# Cansat2019_1516_Payload_SectionA_v03.net
KiCad netlist of a schematic drawn in EAGLE
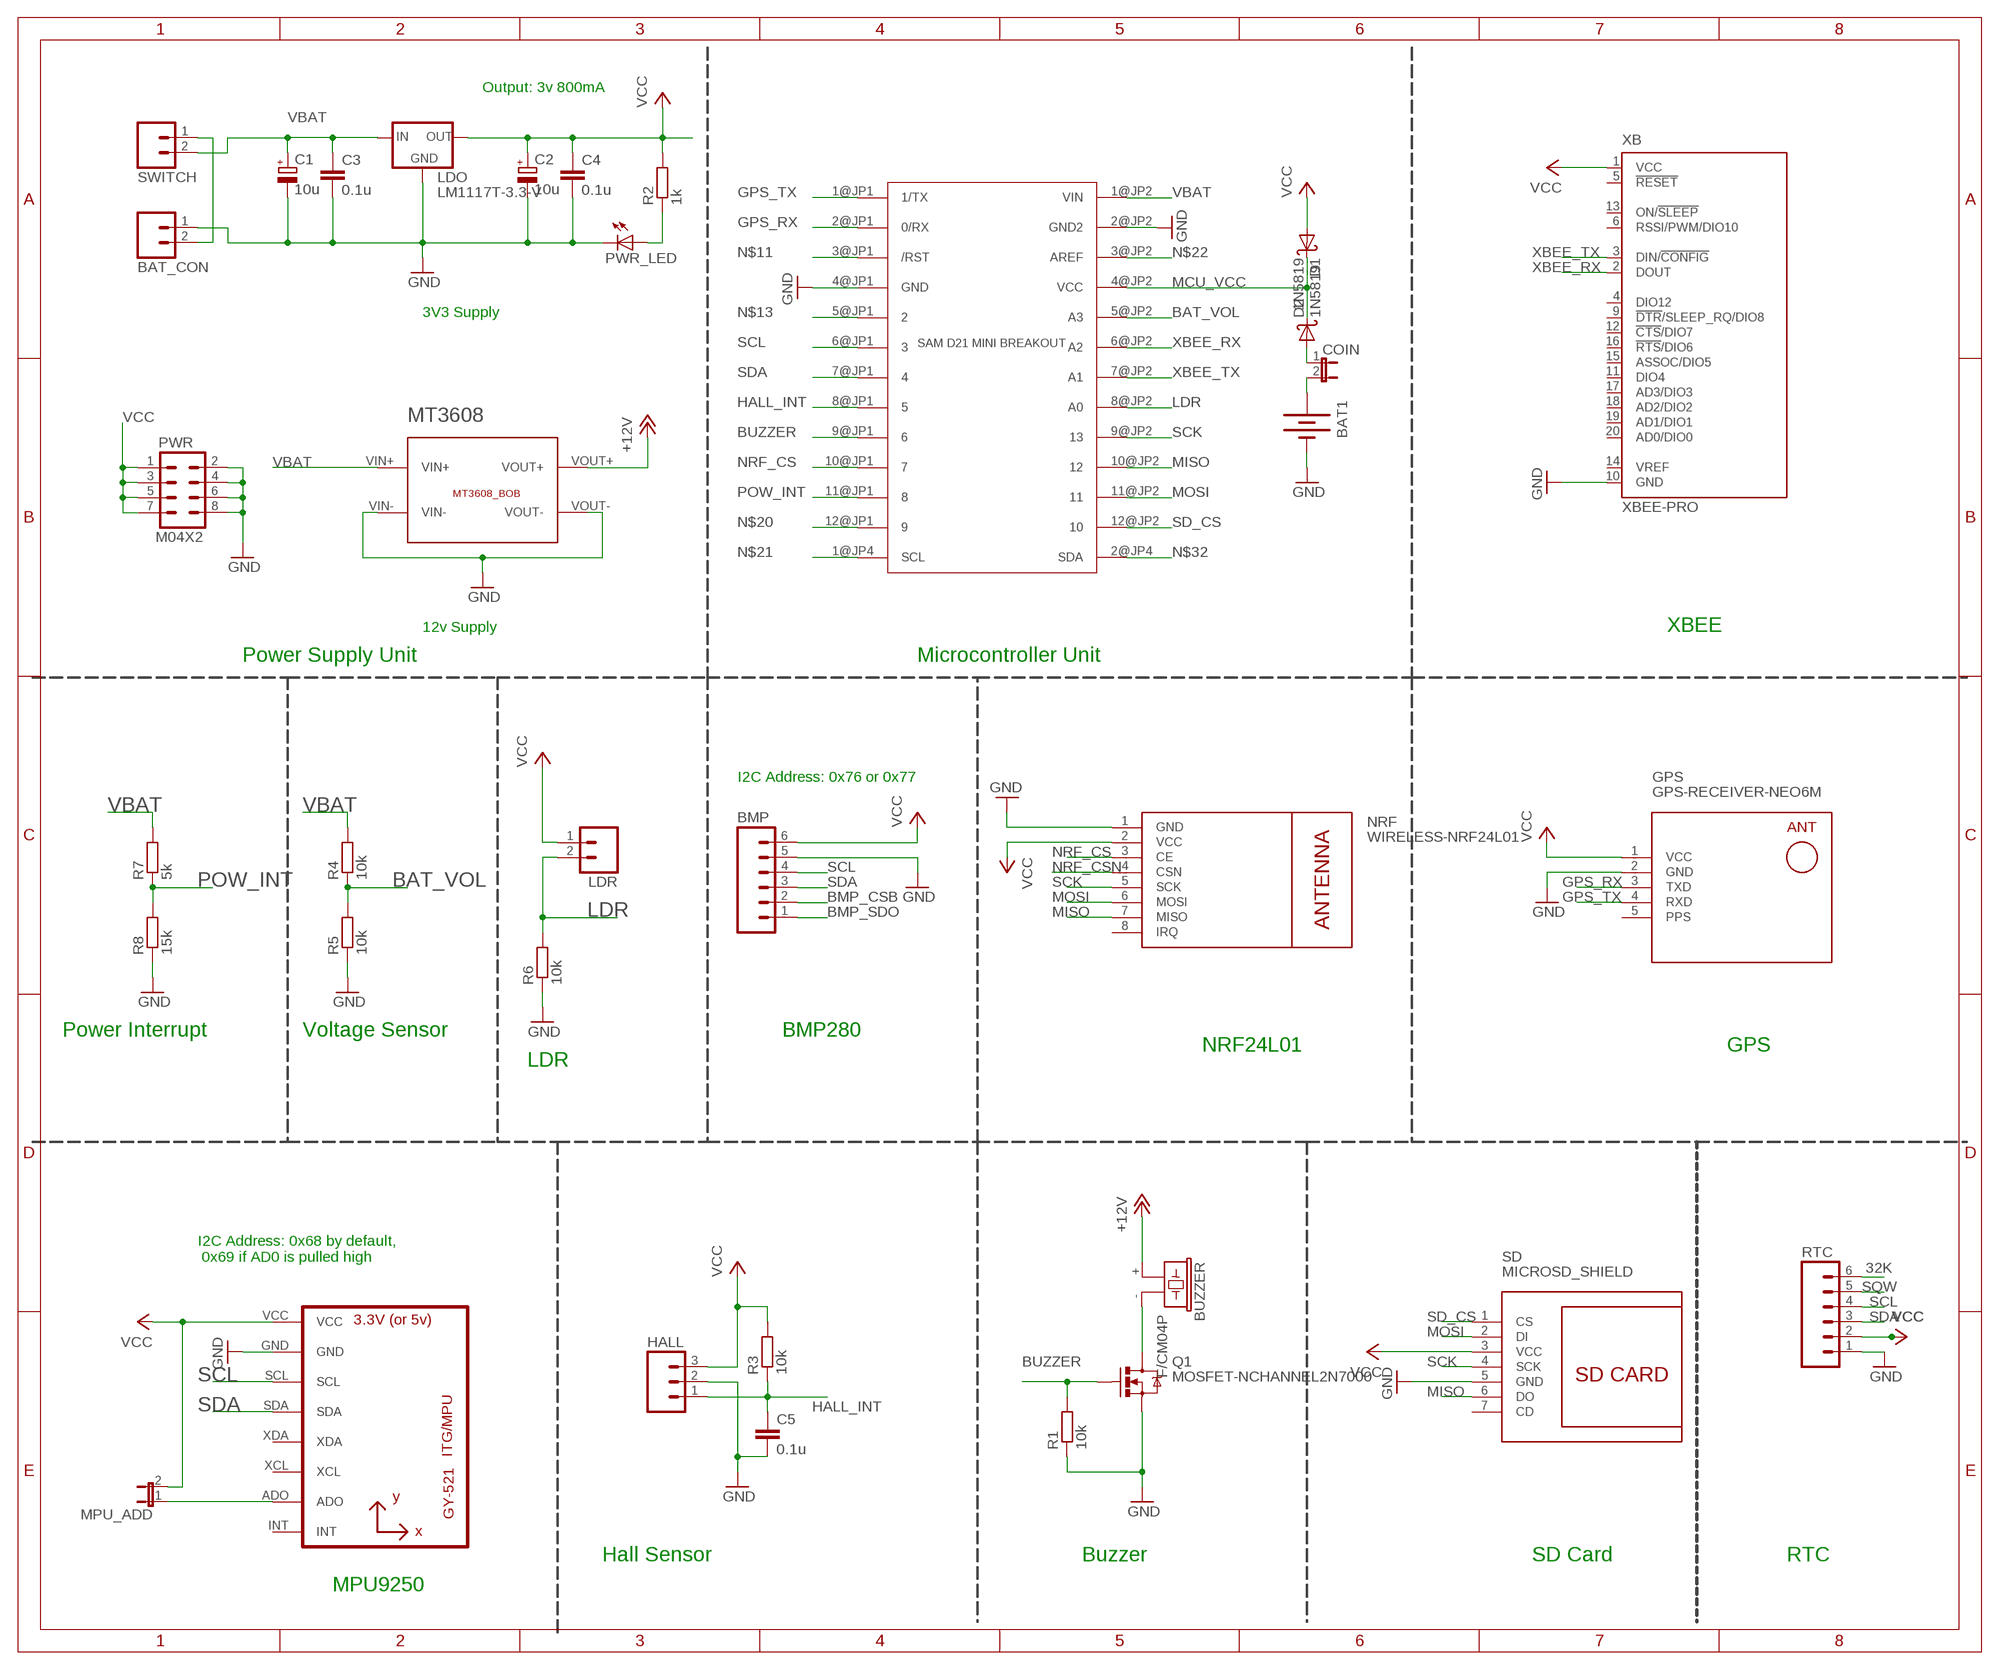
[diagram p0: schematic, sheet 1]

(export (version "E")
  (design (tool "Eeschema 10.0.6"))
  (components
    (comp (ref "BAT1")
      (value "BATTERY20PTH")
      (footprint "eagle-import:BATTCOM_20MM_PTH")
      (libsource (lib "eagle-import") (part "BATTERY20PTH"))
    )
    (comp (ref "BAT_CON")
      (value "M02")
      (footprint "eagle-import:02P")
      (libsource (lib "eagle-import") (part "M02"))
    )
    (comp (ref "BMP")
      (value "M06")
      (footprint "eagle-import:06P")
      (libsource (lib "eagle-import") (part "M06"))
    )
    (comp (ref "BUZZER")
      (value "F/CM04P")
      (footprint "eagle-import:F_CM04P")
      (libsource (lib "eagle-import") (part "F/CM04P"))
    )
    (comp (ref "C1")
      (value "10u")
      (footprint "eagle-import:E2,5-6")
      (libsource (lib "eagle-import") (part "CPOL-EUE2.5-6"))
    )
    (comp (ref "C2")
      (value "10u")
      (footprint "eagle-import:E2,5-6")
      (libsource (lib "eagle-import") (part "CPOL-EUE2.5-6"))
    )
    (comp (ref "C3")
      (value "0.1u")
      (footprint "eagle-import:C025-025X050")
      (libsource (lib "eagle-import") (part "C-EU025-025X050"))
    )
    (comp (ref "C4")
      (value "0.1u")
      (footprint "eagle-import:C025-025X050")
      (libsource (lib "eagle-import") (part "C-EU025-025X050"))
    )
    (comp (ref "C5")
      (value "0.1u")
      (footprint "eagle-import:C025-025X050")
      (libsource (lib "eagle-import") (part "C-EU025-025X050"))
    )
    (comp (ref "COIN")
      (value "JUMPER-2PTH")
      (footprint "eagle-import:1X02")
      (libsource (lib "eagle-import") (part "JUMPER-2PTH"))
    )
    (comp (ref "D1")
      (value "1N5819")
      (footprint "eagle-import:DO41-10")
      (libsource (lib "eagle-import") (part "1N5819"))
    )
    (comp (ref "D2")
      (value "1N5819")
      (footprint "eagle-import:DO41-10")
      (libsource (lib "eagle-import") (part "1N5819"))
    )
    (comp (ref "GPS")
      (value "GPS-RECEIVER-NEO6M")
      (footprint "eagle-import:GPS-RECEIVER-NEO6M")
      (libsource (lib "eagle-import") (part "GPS-RECEIVER-NEO6M"))
    )
    (comp (ref "HALL")
      (value "M03")
      (footprint "eagle-import:03P")
      (libsource (lib "eagle-import") (part "M03"))
    )
    (comp (ref "LDO")
      (value "LM1117T-3.3-V")
      (footprint "eagle-import:TO220V")
      (libsource (lib "eagle-import") (part "LM1117T--V3.3"))
    )
    (comp (ref "LDR")
      (value "M02")
      (footprint "eagle-import:02P")
      (libsource (lib "eagle-import") (part "M02"))
    )
    (comp (ref "MPU")
      (value "GY-521MPU6050")
      (footprint "eagle-import:GY-521")
      (libsource (lib "eagle-import") (part "GY-521MPU6050"))
    )
    (comp (ref "MPU_ADD")
      (value "JUMPER-2PTH")
      (footprint "eagle-import:1X02")
      (libsource (lib "eagle-import") (part "JUMPER-2PTH"))
    )
    (comp (ref "MT3608")
      (value "MT3608_BOB")
      (footprint "eagle-import:MT3608_BOB")
      (libsource (lib "eagle-import") (part "MT3608_BOB"))
    )
    (comp (ref "NRF")
      (value "WIRELESS-NRF24L01")
      (footprint "eagle-import:WIRELESS-NRF24L01")
      (libsource (lib "eagle-import") (part "WIRELESS-NRF24L01"))
    )
    (comp (ref "PWR")
      (value "M04X2")
      (footprint "eagle-import:2X4")
      (libsource (lib "eagle-import") (part "M04X2"))
    )
    (comp (ref "PWR_LED")
      (value "LED3MM")
      (footprint "eagle-import:LED3MM")
      (libsource (lib "eagle-import") (part "LED3MM"))
    )
    (comp (ref "Q1")
      (value "MOSFET-NCHANNEL2N7000")
      (footprint "eagle-import:TO-92")
      (libsource (lib "eagle-import") (part "MOSFET-NCHANNEL2N7000"))
    )
    (comp (ref "R1")
      (value "10k")
      (footprint "eagle-import:0204_7")
      (libsource (lib "eagle-import") (part "R-EU_0204/7"))
    )
    (comp (ref "R2")
      (value "1k")
      (footprint "eagle-import:0204_7")
      (libsource (lib "eagle-import") (part "R-EU_0204/7"))
    )
    (comp (ref "R3")
      (value "10k")
      (footprint "eagle-import:0204_7")
      (libsource (lib "eagle-import") (part "R-EU_0204/7"))
    )
    (comp (ref "R4")
      (value "10k")
      (footprint "eagle-import:0204_7")
      (libsource (lib "eagle-import") (part "R-EU_0204/7"))
    )
    (comp (ref "R5")
      (value "10k")
      (footprint "eagle-import:0204_7")
      (libsource (lib "eagle-import") (part "R-EU_0204/7"))
    )
    (comp (ref "R6")
      (value "10k")
      (footprint "eagle-import:0204_7")
      (libsource (lib "eagle-import") (part "R-EU_0204/7"))
    )
    (comp (ref "R7")
      (value "5k")
      (footprint "eagle-import:0204_7")
      (libsource (lib "eagle-import") (part "R-EU_0204/7"))
    )
    (comp (ref "R8")
      (value "15k")
      (footprint "eagle-import:0204_7")
      (libsource (lib "eagle-import") (part "R-EU_0204/7"))
    )
    (comp (ref "RTC")
      (value "M06")
      (footprint "eagle-import:06P")
      (libsource (lib "eagle-import") (part "M06"))
    )
    (comp (ref "SAMD")
      (value "SAM_D21_MINI_BREAKOUT")
      (footprint "eagle-import:JP1_SPARKFUN-SAMD21-MINI-BREAKOUT-V10")
      (libsource (lib "eagle-import") (part "SAM_D21_MINI_BREAKOUT"))
    )
    (comp (ref "SD")
      (value "MICROSD_SHIELD")
      (footprint "eagle-import:MICROSD_SHIELD")
      (libsource (lib "eagle-import") (part "MICROSD_SHIELD"))
    )
    (comp (ref "SWITCH")
      (value "M02")
      (footprint "eagle-import:02P")
      (libsource (lib "eagle-import") (part "M02"))
    )
    (comp (ref "XB")
      (value "XBEE-PRO")
      (footprint "eagle-import:XBEE-PRO")
      (fields (field (name "MPN") "XBP24-AWI-001"))
      (libsource (lib "eagle-import") (part "XBEE-PRO"))
    )
  )
  (nets
    (net (code "1") (name "+12V") (class "Default")
      (node (ref "BUZZER") (pin "+") (pinfunction "1_+") (pintype "passive"))
      (node (ref "MT3608") (pin "VOUT+") (pinfunction "VOUT+_VOUT+") (pintype "bidirectional"))
    )
    (net (code "2") (name "/32K") (class "Default")
      (node (ref "RTC") (pin "6") (pinfunction "6_6") (pintype "passive"))
    )
    (net (code "3") (name "/BAT_VOL") (class "Default")
      (node (ref "R4") (pin "1") (pinfunction "1_1") (pintype "passive"))
      (node (ref "R5") (pin "2") (pinfunction "2_2") (pintype "passive"))
      (node (ref "SAMD") (pin "5@JP2") (pinfunction "A3_5@JP2") (pintype "bidirectional"))
    )
    (net (code "4") (name "/BMP_CSB") (class "Default")
      (node (ref "BMP") (pin "2") (pinfunction "2_2") (pintype "passive"))
    )
    (net (code "5") (name "/BMP_SDO") (class "Default")
      (node (ref "BMP") (pin "1") (pinfunction "1_1") (pintype "passive"))
    )
    (net (code "6") (name "/BUZZER") (class "Default")
      (node (ref "Q1") (pin "2") (pinfunction "G_2") (pintype "passive"))
      (node (ref "R1") (pin "2") (pinfunction "2_2") (pintype "passive"))
      (node (ref "SAMD") (pin "9@JP1") (pinfunction "6_9@JP1") (pintype "bidirectional"))
    )
    (net (code "7") (name "/GPS_RX") (class "Default")
      (node (ref "GPS") (pin "3") (pinfunction "TXD_3") (pintype "bidirectional"))
      (node (ref "SAMD") (pin "2@JP1") (pinfunction "0/RX_2@JP1") (pintype "bidirectional"))
    )
    (net (code "8") (name "/GPS_TX") (class "Default")
      (node (ref "GPS") (pin "4") (pinfunction "RXD_4") (pintype "power_in"))
      (node (ref "SAMD") (pin "1@JP1") (pinfunction "1/TX_1@JP1") (pintype "bidirectional"))
    )
    (net (code "9") (name "/HALL_INT") (class "Default")
      (node (ref "C5") (pin "1") (pinfunction "1_1") (pintype "passive"))
      (node (ref "HALL") (pin "1") (pinfunction "1_1") (pintype "passive"))
      (node (ref "R3") (pin "1") (pinfunction "1_1") (pintype "passive"))
      (node (ref "SAMD") (pin "8@JP1") (pinfunction "5_8@JP1") (pintype "bidirectional"))
    )
    (net (code "10") (name "/LDR") (class "Default")
      (node (ref "LDR") (pin "2") (pinfunction "2_2") (pintype "passive"))
      (node (ref "R6") (pin "2") (pinfunction "2_2") (pintype "passive"))
      (node (ref "SAMD") (pin "8@JP2") (pinfunction "A0_8@JP2") (pintype "bidirectional"))
    )
    (net (code "11") (name "/MCU_VCC") (class "Default")
      (node (ref "D1") (pin "C") (pinfunction "C_C") (pintype "passive"))
      (node (ref "D2") (pin "C") (pinfunction "C_C") (pintype "passive"))
      (node (ref "SAMD") (pin "4@JP2") (pinfunction "VCC_4@JP2") (pintype "power_in"))
    )
    (net (code "12") (name "/MISO") (class "Default")
      (node (ref "NRF") (pin "7") (pinfunction "MISO_7") (pintype "bidirectional"))
      (node (ref "SAMD") (pin "10@JP2") (pinfunction "12_10@JP2") (pintype "bidirectional"))
      (node (ref "SD") (pin "6") (pinfunction "DO_6") (pintype "bidirectional"))
    )
    (net (code "13") (name "/MOSI") (class "Default")
      (node (ref "NRF") (pin "6") (pinfunction "MOSI_6") (pintype "bidirectional"))
      (node (ref "SAMD") (pin "11@JP2") (pinfunction "11_11@JP2") (pintype "bidirectional"))
      (node (ref "SD") (pin "2") (pinfunction "DI_2") (pintype "bidirectional"))
    )
    (net (code "14") (name "/N$11") (class "Default")
      (node (ref "SAMD") (pin "3@JP1") (pinfunction "/RST_3@JP1") (pintype "input"))
    )
    (net (code "15") (name "/N$13") (class "Default")
      (node (ref "SAMD") (pin "5@JP1") (pinfunction "2_5@JP1") (pintype "bidirectional"))
    )
    (net (code "16") (name "/N$20") (class "Default")
      (node (ref "SAMD") (pin "12@JP1") (pinfunction "9_12@JP1") (pintype "bidirectional"))
    )
    (net (code "17") (name "/N$21") (class "Default")
      (node (ref "SAMD") (pin "1@JP4") (pinfunction "SCL_1@JP4") (pintype "bidirectional"))
    )
    (net (code "18") (name "/N$22") (class "Default")
      (node (ref "SAMD") (pin "3@JP2") (pinfunction "AREF_3@JP2") (pintype "power_in"))
    )
    (net (code "19") (name "/N$32") (class "Default")
      (node (ref "SAMD") (pin "2@JP4") (pinfunction "SDA_2@JP4") (pintype "bidirectional"))
    )
    (net (code "20") (name "/NRF_CS") (class "Default")
      (node (ref "NRF") (pin "3") (pinfunction "CE_3") (pintype "bidirectional"))
      (node (ref "SAMD") (pin "10@JP1") (pinfunction "7_10@JP1") (pintype "bidirectional"))
    )
    (net (code "21") (name "/NRF_CSN") (class "Default")
      (node (ref "NRF") (pin "4") (pinfunction "CSN_4") (pintype "bidirectional"))
    )
    (net (code "22") (name "/POW_INT") (class "Default")
      (node (ref "R7") (pin "1") (pinfunction "1_1") (pintype "passive"))
      (node (ref "R8") (pin "2") (pinfunction "2_2") (pintype "passive"))
      (node (ref "SAMD") (pin "11@JP1") (pinfunction "8_11@JP1") (pintype "bidirectional"))
    )
    (net (code "23") (name "/PPS") (class "Default")
      (node (ref "GPS") (pin "5") (pinfunction "PPS_5") (pintype "power_in"))
    )
    (net (code "24") (name "/SCK") (class "Default")
      (node (ref "NRF") (pin "5") (pinfunction "SCK_5") (pintype "bidirectional"))
      (node (ref "SAMD") (pin "9@JP2") (pinfunction "13_9@JP2") (pintype "bidirectional"))
      (node (ref "SD") (pin "4") (pinfunction "SCK_4") (pintype "bidirectional"))
    )
    (net (code "25") (name "/SCL") (class "Default")
      (node (ref "BMP") (pin "4") (pinfunction "4_4") (pintype "passive"))
      (node (ref "MPU") (pin "SCL") (pinfunction "SCL_SCL") (pintype "bidirectional"))
      (node (ref "RTC") (pin "4") (pinfunction "4_4") (pintype "passive"))
      (node (ref "SAMD") (pin "6@JP1") (pinfunction "3_6@JP1") (pintype "bidirectional"))
    )
    (net (code "26") (name "/SDA") (class "Default")
      (node (ref "BMP") (pin "3") (pinfunction "3_3") (pintype "passive"))
      (node (ref "MPU") (pin "SDA") (pinfunction "SDA_SDA") (pintype "bidirectional"))
      (node (ref "RTC") (pin "3") (pinfunction "3_3") (pintype "passive"))
      (node (ref "SAMD") (pin "7@JP1") (pinfunction "4_7@JP1") (pintype "bidirectional"))
    )
    (net (code "27") (name "/SD_CS") (class "Default")
      (node (ref "SAMD") (pin "12@JP2") (pinfunction "10_12@JP2") (pintype "bidirectional"))
      (node (ref "SD") (pin "1") (pinfunction "CS_1") (pintype "bidirectional"))
    )
    (net (code "28") (name "/SQW") (class "Default")
      (node (ref "RTC") (pin "5") (pinfunction "5_5") (pintype "passive"))
    )
    (net (code "29") (name "/VBAT") (class "Default")
      (node (ref "C1") (pin "+") (pinfunction "+_+") (pintype "passive"))
      (node (ref "C3") (pin "1") (pinfunction "1_1") (pintype "passive"))
      (node (ref "LDO") (pin "3") (pinfunction "IN_3") (pintype "input"))
      (node (ref "MT3608") (pin "VIN+") (pinfunction "VIN+_VIN+") (pintype "bidirectional"))
      (node (ref "R4") (pin "2") (pinfunction "2_2") (pintype "passive"))
      (node (ref "R7") (pin "2") (pinfunction "2_2") (pintype "passive"))
      (node (ref "SAMD") (pin "1@JP2") (pinfunction "VIN_1@JP2") (pintype "power_in"))
      (node (ref "SWITCH") (pin "2") (pinfunction "2_2") (pintype "passive"))
    )
    (net (code "30") (name "/XBEE_RX") (class "Default")
      (node (ref "SAMD") (pin "6@JP2") (pinfunction "A2_6@JP2") (pintype "bidirectional"))
      (node (ref "XB") (pin "2") (pinfunction "DOUT_2") (pintype "output"))
    )
    (net (code "31") (name "/XBEE_TX") (class "Default")
      (node (ref "SAMD") (pin "7@JP2") (pinfunction "A1_7@JP2") (pintype "bidirectional"))
      (node (ref "XB") (pin "3") (pinfunction "DIN/~{CONFIG}_3") (pintype "input"))
    )
    (net (code "32") (name "GND") (class "Default")
      (node (ref "BAT1") (pin "2") (pinfunction "-_2") (pintype "power_in"))
      (node (ref "BAT_CON") (pin "1") (pinfunction "1_1") (pintype "passive"))
      (node (ref "BMP") (pin "5") (pinfunction "5_5") (pintype "passive"))
      (node (ref "C1") (pin "-") (pinfunction "-_-") (pintype "passive"))
      (node (ref "C2") (pin "-") (pinfunction "-_-") (pintype "passive"))
      (node (ref "C3") (pin "2") (pinfunction "2_2") (pintype "passive"))
      (node (ref "C4") (pin "2") (pinfunction "2_2") (pintype "passive"))
      (node (ref "C5") (pin "2") (pinfunction "2_2") (pintype "passive"))
      (node (ref "GPS") (pin "2") (pinfunction "GND_2") (pintype "bidirectional"))
      (node (ref "HALL") (pin "2") (pinfunction "2_2") (pintype "passive"))
      (node (ref "LDO") (pin "1") (pinfunction "GND_1") (pintype "input"))
      (node (ref "MPU") (pin "GND") (pinfunction "GND_GND") (pintype "bidirectional"))
      (node (ref "MT3608") (pin "VIN-") (pinfunction "VIN-_VIN-") (pintype "bidirectional"))
      (node (ref "MT3608") (pin "VOUT-") (pinfunction "VOUT-_VOUT-") (pintype "bidirectional"))
      (node (ref "NRF") (pin "1") (pinfunction "GND_1") (pintype "power_in"))
      (node (ref "PWR") (pin "2") (pinfunction "2_2") (pintype "passive"))
      (node (ref "PWR") (pin "4") (pinfunction "4_4") (pintype "passive"))
      (node (ref "PWR") (pin "6") (pinfunction "6_6") (pintype "passive"))
      (node (ref "PWR") (pin "8") (pinfunction "8_8") (pintype "passive"))
      (node (ref "PWR_LED") (pin "K") (pinfunction "C_K") (pintype "passive"))
      (node (ref "Q1") (pin "1") (pinfunction "S_1") (pintype "passive"))
      (node (ref "R1") (pin "1") (pinfunction "1_1") (pintype "passive"))
      (node (ref "R5") (pin "1") (pinfunction "1_1") (pintype "passive"))
      (node (ref "R6") (pin "1") (pinfunction "1_1") (pintype "passive"))
      (node (ref "R8") (pin "1") (pinfunction "1_1") (pintype "passive"))
      (node (ref "RTC") (pin "1") (pinfunction "1_1") (pintype "passive"))
      (node (ref "SAMD") (pin "2@JP2") (pinfunction "GND2_2@JP2") (pintype "power_in"))
      (node (ref "SAMD") (pin "4@JP1") (pinfunction "GND_4@JP1") (pintype "power_in"))
      (node (ref "SD") (pin "5") (pinfunction "GND_5") (pintype "power_in"))
      (node (ref "XB") (pin "10") (pinfunction "GND_10") (pintype "power_in"))
    )
    (net (code "33") (name "Net-(BAT1-+)") (class "Default")
      (node (ref "BAT1") (pin "1") (pinfunction "+_1") (pintype "power_in"))
      (node (ref "COIN") (pin "2") (pinfunction "2_2") (pintype "passive"))
    )
    (net (code "34") (name "Net-(BAT_CON-Pad2)") (class "Default")
      (node (ref "BAT_CON") (pin "2") (pinfunction "2_2") (pintype "passive"))
      (node (ref "SWITCH") (pin "1") (pinfunction "1_1") (pintype "passive"))
    )
    (net (code "35") (name "Net-(BUZZER-2)") (class "Default")
      (node (ref "BUZZER") (pin "-") (pinfunction "2_-") (pintype "passive"))
      (node (ref "Q1") (pin "3") (pinfunction "D_3") (pintype "passive"))
    )
    (net (code "36") (name "Net-(COIN-Pad1)") (class "Default")
      (node (ref "COIN") (pin "1") (pinfunction "1_1") (pintype "passive"))
      (node (ref "D2") (pin "A") (pinfunction "A_A") (pintype "passive"))
    )
    (net (code "37") (name "Net-(MPU-PadADO)") (class "Default")
      (node (ref "MPU") (pin "ADO") (pinfunction "ADO_ADO") (pintype "bidirectional"))
      (node (ref "MPU_ADD") (pin "1") (pinfunction "1_1") (pintype "passive"))
    )
    (net (code "38") (name "Net-(PWR_LED-PadA)") (class "Default")
      (node (ref "PWR_LED") (pin "A") (pinfunction "A_A") (pintype "passive"))
      (node (ref "R2") (pin "1") (pinfunction "1_1") (pintype "passive"))
    )
    (net (code "39") (name "VCC") (class "Default")
      (node (ref "BMP") (pin "6") (pinfunction "6_6") (pintype "passive"))
      (node (ref "C2") (pin "+") (pinfunction "+_+") (pintype "passive"))
      (node (ref "C4") (pin "1") (pinfunction "1_1") (pintype "passive"))
      (node (ref "D1") (pin "A") (pinfunction "A_A") (pintype "passive"))
      (node (ref "GPS") (pin "1") (pinfunction "VCC_1") (pintype "bidirectional"))
      (node (ref "HALL") (pin "3") (pinfunction "3_3") (pintype "passive"))
      (node (ref "LDO") (pin "2") (pinfunction "OUT_2") (pintype "passive"))
      (node (ref "LDR") (pin "1") (pinfunction "1_1") (pintype "passive"))
      (node (ref "MPU") (pin "VCC") (pinfunction "VCC_VCC") (pintype "bidirectional"))
      (node (ref "MPU_ADD") (pin "2") (pinfunction "2_2") (pintype "passive"))
      (node (ref "NRF") (pin "2") (pinfunction "VCC_2") (pintype "power_in"))
      (node (ref "PWR") (pin "1") (pinfunction "1_1") (pintype "passive"))
      (node (ref "PWR") (pin "3") (pinfunction "3_3") (pintype "passive"))
      (node (ref "PWR") (pin "5") (pinfunction "5_5") (pintype "passive"))
      (node (ref "PWR") (pin "7") (pinfunction "7_7") (pintype "passive"))
      (node (ref "R2") (pin "2") (pinfunction "2_2") (pintype "passive"))
      (node (ref "R3") (pin "2") (pinfunction "2_2") (pintype "passive"))
      (node (ref "RTC") (pin "2") (pinfunction "2_2") (pintype "passive"))
      (node (ref "SD") (pin "3") (pinfunction "VCC_3") (pintype "power_in"))
      (node (ref "XB") (pin "1") (pinfunction "VCC_1") (pintype "power_in"))
    )
    (net (code "40") (name "unconnected-(MPU-PadINT)") (class "Default")
      (node (ref "MPU") (pin "INT") (pinfunction "INT_INT") (pintype "bidirectional"))
    )
    (net (code "41") (name "unconnected-(MPU-PadXCL)") (class "Default")
      (node (ref "MPU") (pin "XCL") (pinfunction "XCL_XCL") (pintype "bidirectional"))
    )
    (net (code "42") (name "unconnected-(MPU-PadXDA)") (class "Default")
      (node (ref "MPU") (pin "XDA") (pinfunction "XDA_XDA") (pintype "bidirectional"))
    )
    (net (code "43") (name "unconnected-(NRF-IRQ-Pad8)") (class "Default")
      (node (ref "NRF") (pin "8") (pinfunction "IRQ_8") (pintype "bidirectional"))
    )
    (net (code "44") (name "unconnected-(SD-CD-Pad7)") (class "Default")
      (node (ref "SD") (pin "7") (pinfunction "CD_7") (pintype "bidirectional"))
    )
    (net (code "45") (name "unconnected-(XB-AD0{slash}DIO0-Pad20)") (class "Default")
      (node (ref "XB") (pin "20") (pinfunction "AD0/DIO0_20") (pintype "bidirectional"))
    )
    (net (code "46") (name "unconnected-(XB-AD1{slash}DIO1-Pad19)") (class "Default")
      (node (ref "XB") (pin "19") (pinfunction "AD1/DIO1_19") (pintype "bidirectional"))
    )
    (net (code "47") (name "unconnected-(XB-AD2{slash}DIO2-Pad18)") (class "Default")
      (node (ref "XB") (pin "18") (pinfunction "AD2/DIO2_18") (pintype "bidirectional"))
    )
    (net (code "48") (name "unconnected-(XB-AD3{slash}DIO3-Pad17)") (class "Default")
      (node (ref "XB") (pin "17") (pinfunction "AD3/DIO3_17") (pintype "bidirectional"))
    )
    (net (code "49") (name "unconnected-(XB-ASSOC{slash}DIO5-Pad15)") (class "Default")
      (node (ref "XB") (pin "15") (pinfunction "ASSOC/DIO5_15") (pintype "bidirectional"))
    )
    (net (code "50") (name "unconnected-(XB-DIO4-Pad11)") (class "Default")
      (node (ref "XB") (pin "11") (pinfunction "DIO4_11") (pintype "bidirectional"))
    )
    (net (code "51") (name "unconnected-(XB-DIO12-Pad4)") (class "Default")
      (node (ref "XB") (pin "4") (pinfunction "DIO12_4") (pintype "bidirectional"))
    )
    (net (code "52") (name "unconnected-(XB-ON{slash}~{SLEEP}-Pad13)") (class "Default")
      (node (ref "XB") (pin "13") (pinfunction "ON/~{SLEEP}_13") (pintype "output"))
    )
    (net (code "53") (name "unconnected-(XB-RSSI{slash}PWM{slash}DIO10-Pad6)") (class "Default")
      (node (ref "XB") (pin "6") (pinfunction "RSSI/PWM/DIO10_6") (pintype "output"))
    )
    (net (code "54") (name "unconnected-(XB-VREF-Pad14)") (class "Default")
      (node (ref "XB") (pin "14") (pinfunction "VREF_14") (pintype "input"))
    )
    (net (code "55") (name "unconnected-(XB-~{CTS}{slash}DIO7-Pad12)") (class "Default")
      (node (ref "XB") (pin "12") (pinfunction "~{CTS}/DIO7_12") (pintype "bidirectional"))
    )
    (net (code "56") (name "unconnected-(XB-~{DTR}{slash}SLEEP_RQ{slash}DIO8-Pad9)") (class "Default")
      (node (ref "XB") (pin "9") (pinfunction "~{DTR}/SLEEP_RQ/DIO8_9") (pintype "bidirectional"))
    )
    (net (code "57") (name "unconnected-(XB-~{RESET}-Pad5)") (class "Default")
      (node (ref "XB") (pin "5") (pinfunction "~{RESET}_5") (pintype "input"))
    )
    (net (code "58") (name "unconnected-(XB-~{RTS}{slash}DIO6-Pad16)") (class "Default")
      (node (ref "XB") (pin "16") (pinfunction "~{RTS}/DIO6_16") (pintype "bidirectional"))
    )
  )
)
